# eps-v1-1.net
KiCad netlist of a schematic drawn in EAGLE
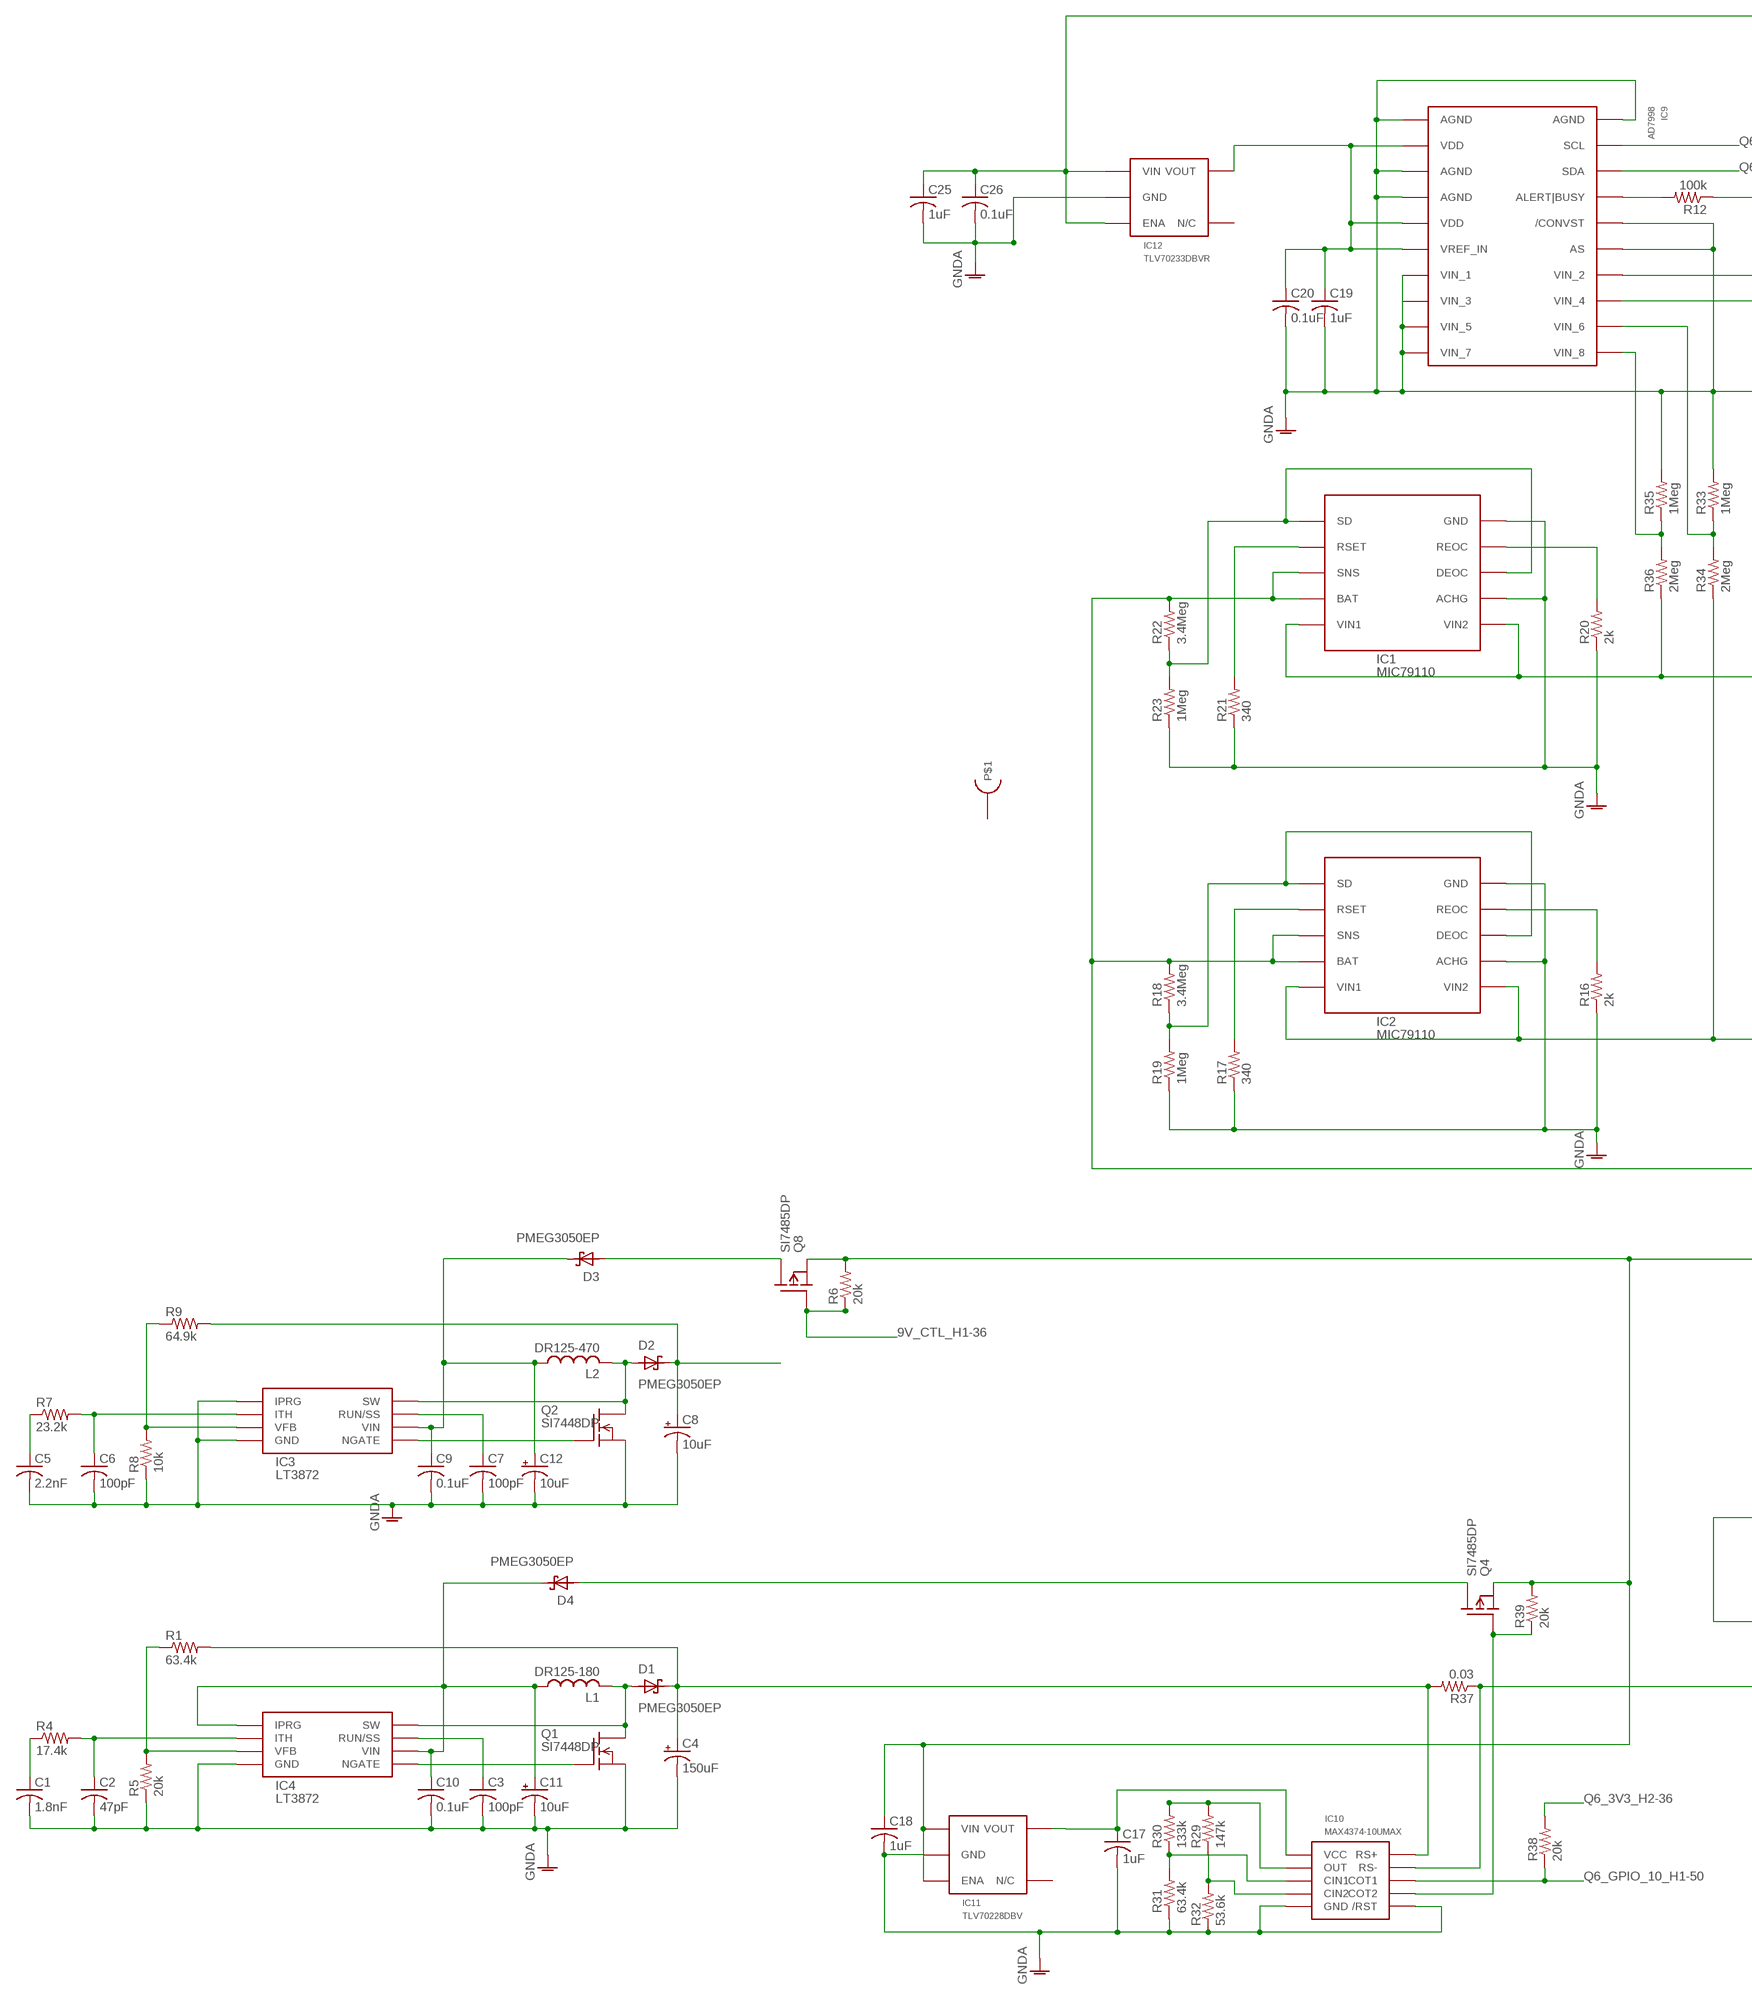
[diagram p0: schematic, sheet 1, part 1 of 2]
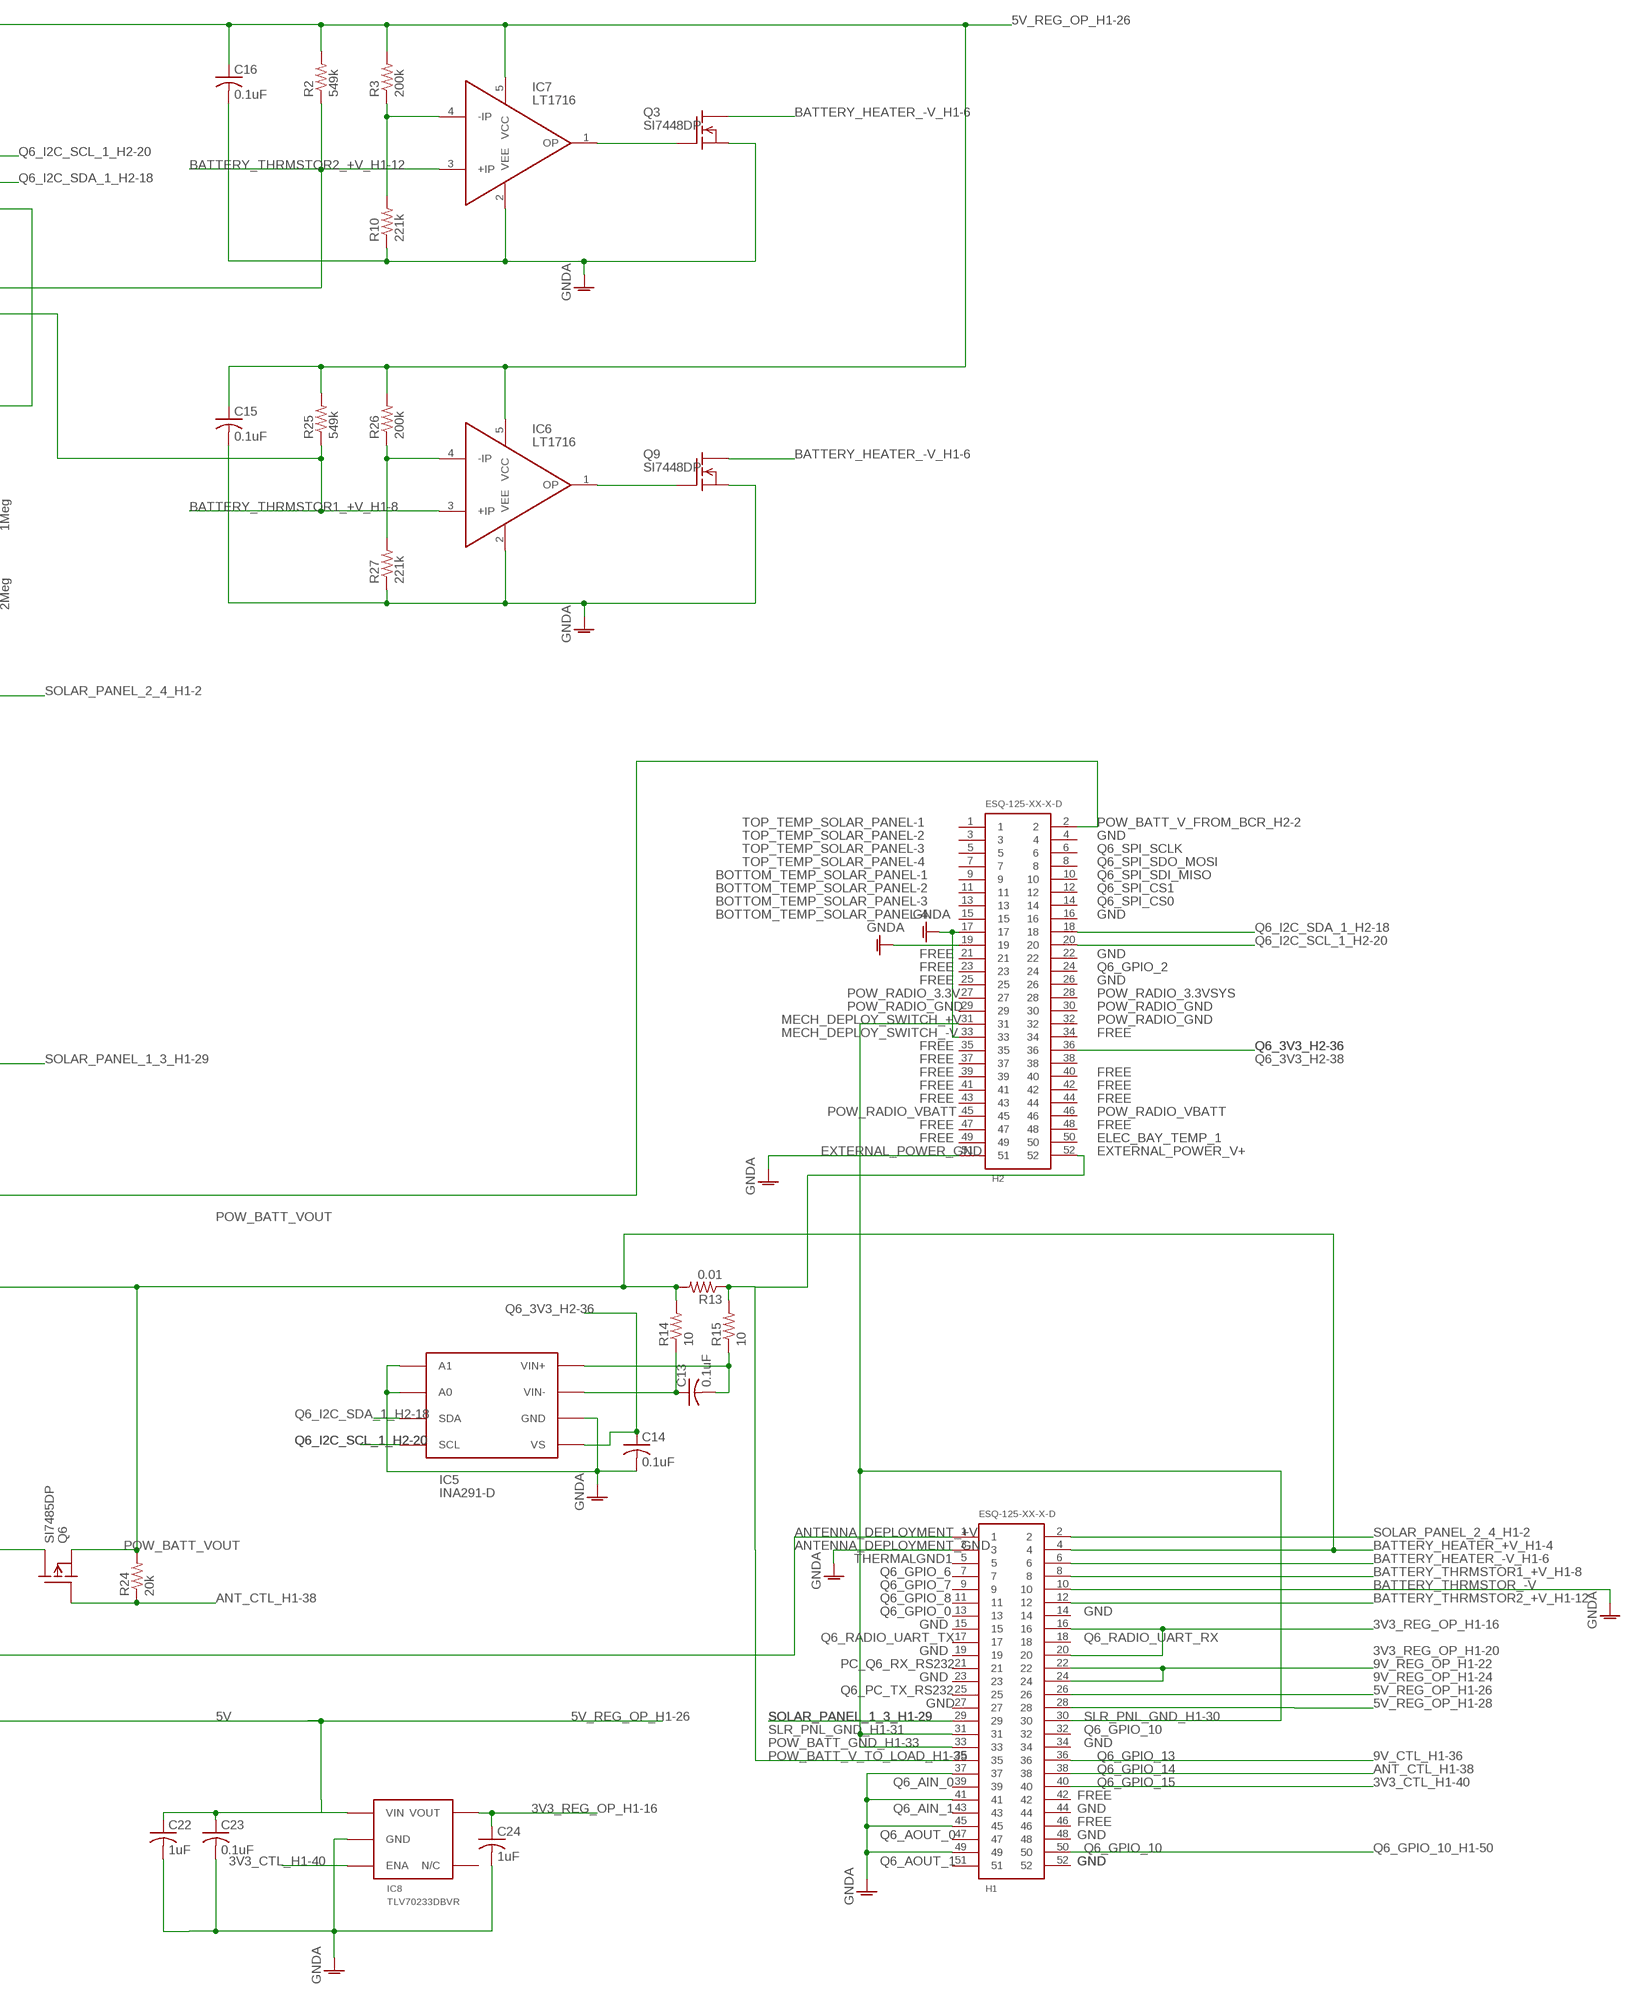
[diagram p1: schematic, sheet 1, part 2 of 2]

(export (version "E")
  (design (tool "Eeschema 10.0.6"))
  (components
    (comp (ref "C1")
      (value "1.8nF")
      (footprint "eagle-import:C0805")
      (libsource (lib "eagle-import") (part "C-USC0805"))
    )
    (comp (ref "C2")
      (value "47pF")
      (footprint "eagle-import:C0805")
      (libsource (lib "eagle-import") (part "C-USC0805"))
    )
    (comp (ref "C3")
      (value "100pF")
      (footprint "eagle-import:C0805")
      (libsource (lib "eagle-import") (part "C-USC0805"))
    )
    (comp (ref "C4")
      (value "150uF")
      (footprint "eagle-import:D_7343-31R")
      (libsource (lib "eagle-import") (part "CPOL-USD/7343-31R"))
    )
    (comp (ref "C5")
      (value "2.2nF")
      (footprint "eagle-import:C0805")
      (libsource (lib "eagle-import") (part "C-USC0805"))
    )
    (comp (ref "C6")
      (value "100pF")
      (footprint "eagle-import:C0805")
      (libsource (lib "eagle-import") (part "C-USC0805"))
    )
    (comp (ref "C7")
      (value "100pF")
      (footprint "eagle-import:C0805")
      (libsource (lib "eagle-import") (part "C-USC0805"))
    )
    (comp (ref "C8")
      (value "10uF")
      (footprint "eagle-import:D_7343-31R")
      (libsource (lib "eagle-import") (part "CPOL-USD/7343-31R"))
    )
    (comp (ref "C9")
      (value "0.1uF")
      (footprint "eagle-import:C0805")
      (libsource (lib "eagle-import") (part "C-USC0805"))
    )
    (comp (ref "C10")
      (value "0.1uF")
      (footprint "eagle-import:C0805")
      (libsource (lib "eagle-import") (part "C-USC0805"))
    )
    (comp (ref "C11")
      (value "10uF")
      (footprint "eagle-import:D_7343-31R")
      (libsource (lib "eagle-import") (part "CPOL-USD/7343-31R"))
    )
    (comp (ref "C12")
      (value "10uF")
      (footprint "eagle-import:D_7343-31R")
      (libsource (lib "eagle-import") (part "CPOL-USD/7343-31R"))
    )
    (comp (ref "C13")
      (value "0.1uF")
      (footprint "eagle-import:C0805")
      (libsource (lib "eagle-import") (part "C-USC0805"))
    )
    (comp (ref "C14")
      (value "0.1uF")
      (footprint "eagle-import:C0805")
      (libsource (lib "eagle-import") (part "C-USC0805"))
    )
    (comp (ref "C15")
      (value "0.1uF")
      (footprint "eagle-import:C0805")
      (libsource (lib "eagle-import") (part "C-USC0805"))
    )
    (comp (ref "C16")
      (value "0.1uF")
      (footprint "eagle-import:C0805")
      (libsource (lib "eagle-import") (part "C-USC0805"))
    )
    (comp (ref "C17")
      (value "1uF")
      (footprint "eagle-import:C0805")
      (libsource (lib "eagle-import") (part "C-USC0805"))
    )
    (comp (ref "C18")
      (value "1uF")
      (footprint "eagle-import:C0805")
      (libsource (lib "eagle-import") (part "C-USC0805"))
    )
    (comp (ref "C19")
      (value "1uF")
      (footprint "eagle-import:C0805")
      (libsource (lib "eagle-import") (part "C-USC0805"))
    )
    (comp (ref "C20")
      (value "0.1uF")
      (footprint "eagle-import:C0805")
      (libsource (lib "eagle-import") (part "C-USC0805"))
    )
    (comp (ref "C22")
      (value "1uF")
      (footprint "eagle-import:C0805")
      (libsource (lib "eagle-import") (part "C-USC0805"))
    )
    (comp (ref "C23")
      (value "0.1uF")
      (footprint "eagle-import:C0805")
      (libsource (lib "eagle-import") (part "C-USC0805"))
    )
    (comp (ref "C24")
      (value "1uF")
      (footprint "eagle-import:C0805")
      (libsource (lib "eagle-import") (part "C-USC0805"))
    )
    (comp (ref "C25")
      (value "1uF")
      (footprint "eagle-import:C0805")
      (libsource (lib "eagle-import") (part "C-USC0805"))
    )
    (comp (ref "C26")
      (value "0.1uF")
      (footprint "eagle-import:C0805")
      (libsource (lib "eagle-import") (part "C-USC0805"))
    )
    (comp (ref "D1")
      (value "PMEG3050EP")
      (footprint "eagle-import:SOD128")
      (libsource (lib "eagle-import") (part "PMEG3050EP"))
    )
    (comp (ref "D2")
      (value "PMEG3050EP")
      (footprint "eagle-import:SOD128")
      (libsource (lib "eagle-import") (part "PMEG3050EP"))
    )
    (comp (ref "D3")
      (value "PMEG3050EP")
      (footprint "eagle-import:SOD128")
      (libsource (lib "eagle-import") (part "PMEG3050EP"))
    )
    (comp (ref "D4")
      (value "PMEG3050EP")
      (footprint "eagle-import:SOD128")
      (libsource (lib "eagle-import") (part "PMEG3050EP"))
    )
    (comp (ref "H1")
      (value "ESQ-125-XX-X-D")
      (footprint "eagle-import:ESQ-125-XX-X-D")
      (libsource (lib "eagle-import") (part "ESQ-125-XX-X-D"))
    )
    (comp (ref "H2")
      (value "ESQ-125-XX-X-D")
      (footprint "eagle-import:ESQ-125-XX-X-D")
      (libsource (lib "eagle-import") (part "ESQ-125-XX-X-D"))
    )
    (comp (ref "IC1")
      (value "MIC79110")
      (footprint "eagle-import:MLF10-EP")
      (libsource (lib "eagle-import") (part "MIC79110"))
    )
    (comp (ref "IC2")
      (value "MIC79110")
      (footprint "eagle-import:MLF10-EP")
      (libsource (lib "eagle-import") (part "MIC79110"))
    )
    (comp (ref "IC3")
      (value "LT3872")
      (footprint "eagle-import:TSOT23-8")
      (libsource (lib "eagle-import") (part "LT3872"))
    )
    (comp (ref "IC4")
      (value "LT3872")
      (footprint "eagle-import:TSOT23-8")
      (libsource (lib "eagle-import") (part "LT3872"))
    )
    (comp (ref "IC5")
      (value "INA291-D")
      (footprint "eagle-import:SO08")
      (libsource (lib "eagle-import") (part "INA291-D"))
    )
    (comp (ref "IC6")
      (value "LT1716")
      (footprint "eagle-import:SOT23-5")
      (libsource (lib "eagle-import") (part "LT1716"))
    )
    (comp (ref "IC7")
      (value "LT1716")
      (footprint "eagle-import:SOT23-5")
      (libsource (lib "eagle-import") (part "LT1716"))
    )
    (comp (ref "IC8")
      (value "TLV70233DBVR")
      (footprint "eagle-import:SOT23-5")
      (libsource (lib "eagle-import") (part "TLV70233DBVR"))
    )
    (comp (ref "IC9")
      (value "AD7998")
      (footprint "eagle-import:TSSOP-20")
      (libsource (lib "eagle-import") (part "AD7998"))
    )
    (comp (ref "IC10")
      (value "MAX4374-10UMAX")
      (footprint "eagle-import:10UMAX")
      (libsource (lib "eagle-import") (part "MAX4374-10UMAX"))
    )
    (comp (ref "IC11")
      (value "TLV70228DBV")
      (footprint "eagle-import:SOT23-5")
      (libsource (lib "eagle-import") (part "TLV70228DBV"))
    )
    (comp (ref "IC12")
      (value "TLV70233DBVR")
      (footprint "eagle-import:SOT23-5")
      (libsource (lib "eagle-import") (part "TLV70233DBVR"))
    )
    (comp (ref "L1")
      (value "DR125-180")
      (footprint "eagle-import:DR125")
      (libsource (lib "eagle-import") (part "DR125-180"))
    )
    (comp (ref "L2")
      (value "DR125-470")
      (footprint "eagle-import:DR125")
      (libsource (lib "eagle-import") (part "DR125-470"))
    )
    (comp (ref "Q1")
      (value "SI7448DP")
      (footprint "eagle-import:PPAK-SO08-EP")
      (libsource (lib "eagle-import") (part "SI7448DP"))
    )
    (comp (ref "Q2")
      (value "SI7448DP")
      (footprint "eagle-import:PPAK-SO08-EP")
      (libsource (lib "eagle-import") (part "SI7448DP"))
    )
    (comp (ref "Q3")
      (value "SI7448DP")
      (footprint "eagle-import:PPAK-SO08-EP")
      (libsource (lib "eagle-import") (part "SI7448DP"))
    )
    (comp (ref "Q4")
      (value "SI7485DP")
      (footprint "eagle-import:PPAK-SO08-EP")
      (libsource (lib "eagle-import") (part "SI7485DP"))
    )
    (comp (ref "Q6")
      (value "SI7485DP")
      (footprint "eagle-import:PPAK-SO08-EP")
      (libsource (lib "eagle-import") (part "SI7485DP"))
    )
    (comp (ref "Q8")
      (value "SI7485DP")
      (footprint "eagle-import:PPAK-SO08-EP")
      (libsource (lib "eagle-import") (part "SI7485DP"))
    )
    (comp (ref "Q9")
      (value "SI7448DP")
      (footprint "eagle-import:PPAK-SO08-EP")
      (libsource (lib "eagle-import") (part "SI7448DP"))
    )
    (comp (ref "R1")
      (value "63.4k")
      (footprint "eagle-import:M1206")
      (libsource (lib "eagle-import") (part "R-US_M1206"))
    )
    (comp (ref "R2")
      (value "549k")
      (footprint "eagle-import:M1206")
      (libsource (lib "eagle-import") (part "R-US_M1206"))
    )
    (comp (ref "R3")
      (value "200k")
      (footprint "eagle-import:M1206")
      (libsource (lib "eagle-import") (part "R-US_M1206"))
    )
    (comp (ref "R4")
      (value "17.4k")
      (footprint "eagle-import:M1206")
      (libsource (lib "eagle-import") (part "R-US_M1206"))
    )
    (comp (ref "R5")
      (value "20k")
      (footprint "eagle-import:M1206")
      (libsource (lib "eagle-import") (part "R-US_M1206"))
    )
    (comp (ref "R6")
      (value "20k")
      (footprint "eagle-import:M1206")
      (libsource (lib "eagle-import") (part "R-US_M1206"))
    )
    (comp (ref "R7")
      (value "23.2k")
      (footprint "eagle-import:M1206")
      (libsource (lib "eagle-import") (part "R-US_M1206"))
    )
    (comp (ref "R8")
      (value "10k")
      (footprint "eagle-import:M1206")
      (libsource (lib "eagle-import") (part "R-US_M1206"))
    )
    (comp (ref "R9")
      (value "64.9k")
      (footprint "eagle-import:M1206")
      (libsource (lib "eagle-import") (part "R-US_M1206"))
    )
    (comp (ref "R10")
      (value "221k")
      (footprint "eagle-import:M1206")
      (libsource (lib "eagle-import") (part "R-US_M1206"))
    )
    (comp (ref "R12")
      (value "100k")
      (footprint "eagle-import:M1206")
      (libsource (lib "eagle-import") (part "R-US_M1206"))
    )
    (comp (ref "R13")
      (value "0.01")
      (footprint "eagle-import:M1206")
      (libsource (lib "eagle-import") (part "R-US_M1206"))
    )
    (comp (ref "R14")
      (value "10")
      (footprint "eagle-import:M1206")
      (libsource (lib "eagle-import") (part "R-US_M1206"))
    )
    (comp (ref "R15")
      (value "10")
      (footprint "eagle-import:M1206")
      (libsource (lib "eagle-import") (part "R-US_M1206"))
    )
    (comp (ref "R16")
      (value "2k")
      (footprint "eagle-import:M1206")
      (libsource (lib "eagle-import") (part "R-US_M1206"))
    )
    (comp (ref "R17")
      (value "340")
      (footprint "eagle-import:M1206")
      (libsource (lib "eagle-import") (part "R-US_M1206"))
    )
    (comp (ref "R18")
      (value "3.4Meg")
      (footprint "eagle-import:M1206")
      (libsource (lib "eagle-import") (part "R-US_M1206"))
    )
    (comp (ref "R19")
      (value "1Meg")
      (footprint "eagle-import:M1206")
      (libsource (lib "eagle-import") (part "R-US_M1206"))
    )
    (comp (ref "R20")
      (value "2k")
      (footprint "eagle-import:M1206")
      (libsource (lib "eagle-import") (part "R-US_M1206"))
    )
    (comp (ref "R21")
      (value "340")
      (footprint "eagle-import:M1206")
      (libsource (lib "eagle-import") (part "R-US_M1206"))
    )
    (comp (ref "R22")
      (value "3.4Meg")
      (footprint "eagle-import:M1206")
      (libsource (lib "eagle-import") (part "R-US_M1206"))
    )
    (comp (ref "R23")
      (value "1Meg")
      (footprint "eagle-import:M1206")
      (libsource (lib "eagle-import") (part "R-US_M1206"))
    )
    (comp (ref "R24")
      (value "20k")
      (footprint "eagle-import:M1206")
      (libsource (lib "eagle-import") (part "R-US_M1206"))
    )
    (comp (ref "R25")
      (value "549k")
      (footprint "eagle-import:M1206")
      (libsource (lib "eagle-import") (part "R-US_M1206"))
    )
    (comp (ref "R26")
      (value "200k")
      (footprint "eagle-import:M1206")
      (libsource (lib "eagle-import") (part "R-US_M1206"))
    )
    (comp (ref "R27")
      (value "221k")
      (footprint "eagle-import:M1206")
      (libsource (lib "eagle-import") (part "R-US_M1206"))
    )
    (comp (ref "R29")
      (value "147k")
      (footprint "eagle-import:M1206")
      (libsource (lib "eagle-import") (part "R-US_M1206"))
    )
    (comp (ref "R30")
      (value "133k")
      (footprint "eagle-import:M1206")
      (libsource (lib "eagle-import") (part "R-US_M1206"))
    )
    (comp (ref "R31")
      (value "63.4k")
      (footprint "eagle-import:M1206")
      (libsource (lib "eagle-import") (part "R-US_M1206"))
    )
    (comp (ref "R32")
      (value "53.6k")
      (footprint "eagle-import:M1206")
      (libsource (lib "eagle-import") (part "R-US_M1206"))
    )
    (comp (ref "R33")
      (value "1Meg")
      (footprint "eagle-import:M1206")
      (libsource (lib "eagle-import") (part "R-US_M1206"))
    )
    (comp (ref "R34")
      (value "2Meg")
      (footprint "eagle-import:M1206")
      (libsource (lib "eagle-import") (part "R-US_M1206"))
    )
    (comp (ref "R35")
      (value "1Meg")
      (footprint "eagle-import:M1206")
      (libsource (lib "eagle-import") (part "R-US_M1206"))
    )
    (comp (ref "R36")
      (value "2Meg")
      (footprint "eagle-import:M1206")
      (libsource (lib "eagle-import") (part "R-US_M1206"))
    )
    (comp (ref "R37")
      (value "0.03")
      (footprint "eagle-import:M1206")
      (libsource (lib "eagle-import") (part "R-US_M1206"))
    )
    (comp (ref "R38")
      (value "20k")
      (footprint "eagle-import:M1206")
      (libsource (lib "eagle-import") (part "R-US_M1206"))
    )
    (comp (ref "R39")
      (value "20k")
      (footprint "eagle-import:M1206")
      (libsource (lib "eagle-import") (part "R-US_M1206"))
    )
    (comp (ref "U$1")
      (value "EPS_PCB_THRM_PAD")
      (footprint "eagle-import:EPS_PCB_THRM_PAD")
      (libsource (lib "eagle-import") (part "EPS_PCB_THRM_PAD"))
    )
  )
  (nets
    (net (code "1") (name "/3V3_CTL_H1-40") (class "Default")
      (node (ref "H1") (pin "40") (pinfunction "40_40") (pintype "bidirectional"))
      (node (ref "IC8") (pin "3") (pinfunction "ENA_3") (pintype "bidirectional"))
    )
    (net (code "2") (name "/3V3_REG_OP_H1-16") (class "Default")
      (node (ref "C24") (pin "1") (pinfunction "1_1") (pintype "passive"))
      (node (ref "H1") (pin "16") (pinfunction "16_16") (pintype "bidirectional"))
      (node (ref "H1") (pin "20") (pinfunction "20_20") (pintype "bidirectional"))
      (node (ref "IC8") (pin "5") (pinfunction "VOUT_5") (pintype "bidirectional"))
    )
    (net (code "3") (name "/5V_REG_OP_H1-26") (class "Default")
      (node (ref "C15") (pin "1") (pinfunction "1_1") (pintype "passive"))
      (node (ref "C16") (pin "1") (pinfunction "1_1") (pintype "passive"))
      (node (ref "C22") (pin "1") (pinfunction "1_1") (pintype "passive"))
      (node (ref "C23") (pin "1") (pinfunction "1_1") (pintype "passive"))
      (node (ref "C25") (pin "1") (pinfunction "1_1") (pintype "passive"))
      (node (ref "C26") (pin "1") (pinfunction "1_1") (pintype "passive"))
      (node (ref "H1") (pin "26") (pinfunction "26_26") (pintype "bidirectional"))
      (node (ref "H1") (pin "28") (pinfunction "28_28") (pintype "bidirectional"))
      (node (ref "IC10") (pin "P$9") (pinfunction "RS-_P$9") (pintype "bidirectional"))
      (node (ref "IC12") (pin "1") (pinfunction "VIN_1") (pintype "bidirectional"))
      (node (ref "IC12") (pin "3") (pinfunction "ENA_3") (pintype "bidirectional"))
      (node (ref "IC6") (pin "5") (pinfunction "VCC_5") (pintype "bidirectional"))
      (node (ref "IC7") (pin "5") (pinfunction "VCC_5") (pintype "bidirectional"))
      (node (ref "IC8") (pin "1") (pinfunction "VIN_1") (pintype "bidirectional"))
      (node (ref "R2") (pin "2") (pinfunction "2_2") (pintype "passive"))
      (node (ref "R25") (pin "2") (pinfunction "2_2") (pintype "passive"))
      (node (ref "R26") (pin "2") (pinfunction "2_2") (pintype "passive"))
      (node (ref "R3") (pin "2") (pinfunction "2_2") (pintype "passive"))
      (node (ref "R37") (pin "1") (pinfunction "1_1") (pintype "passive"))
    )
    (net (code "4") (name "/9V_CTL_H1-36") (class "Default")
      (node (ref "H1") (pin "36") (pinfunction "36_36") (pintype "bidirectional"))
      (node (ref "Q8") (pin "P$4-G") (pinfunction "G_P$4-G") (pintype "passive"))
      (node (ref "R6") (pin "1") (pinfunction "1_1") (pintype "passive"))
    )
    (net (code "5") (name "/9V_REG_OP_H1-22") (class "Default")
      (node (ref "C8") (pin "+") (pinfunction "+_+") (pintype "passive"))
      (node (ref "D2") (pin "P$1-CATHODE") (pinfunction "P$1-CATHODE_P$1-CATHODE") (pintype "bidirectional"))
      (node (ref "H1") (pin "22") (pinfunction "22_22") (pintype "bidirectional"))
      (node (ref "H1") (pin "24") (pinfunction "24_24") (pintype "bidirectional"))
      (node (ref "R9") (pin "2") (pinfunction "2_2") (pintype "passive"))
    )
    (net (code "6") (name "/ANT_CTL_H1-38") (class "Default")
      (node (ref "H1") (pin "38") (pinfunction "38_38") (pintype "bidirectional"))
      (node (ref "Q6") (pin "P$4-G") (pinfunction "G_P$4-G") (pintype "passive"))
      (node (ref "R24") (pin "1") (pinfunction "1_1") (pintype "passive"))
    )
    (net (code "7") (name "/BATTERY_HEATER_-V_H1-6") (class "Default")
      (node (ref "H1") (pin "6") (pinfunction "6_6") (pintype "bidirectional"))
      (node (ref "Q3") (pin "P$10-D") (pinfunction "D_P$10-D") (pintype "passive"))
      (node (ref "Q3") (pin "P$11-D") (pinfunction "D_P$11-D") (pintype "passive"))
      (node (ref "Q3") (pin "P$5-D") (pinfunction "D_P$5-D") (pintype "passive"))
      (node (ref "Q3") (pin "P$6-D") (pinfunction "D_P$6-D") (pintype "passive"))
      (node (ref "Q3") (pin "P$7-D") (pinfunction "D_P$7-D") (pintype "passive"))
      (node (ref "Q3") (pin "P$8-D") (pinfunction "D_P$8-D") (pintype "passive"))
      (node (ref "Q3") (pin "P$9-D") (pinfunction "D_P$9-D") (pintype "passive"))
      (node (ref "Q9") (pin "P$10-D") (pinfunction "D_P$10-D") (pintype "passive"))
      (node (ref "Q9") (pin "P$11-D") (pinfunction "D_P$11-D") (pintype "passive"))
      (node (ref "Q9") (pin "P$5-D") (pinfunction "D_P$5-D") (pintype "passive"))
      (node (ref "Q9") (pin "P$6-D") (pinfunction "D_P$6-D") (pintype "passive"))
      (node (ref "Q9") (pin "P$7-D") (pinfunction "D_P$7-D") (pintype "passive"))
      (node (ref "Q9") (pin "P$8-D") (pinfunction "D_P$8-D") (pintype "passive"))
      (node (ref "Q9") (pin "P$9-D") (pinfunction "D_P$9-D") (pintype "passive"))
    )
    (net (code "8") (name "/BATTERY_THRMSTOR1_+V_H1-8") (class "Default")
      (node (ref "H1") (pin "8") (pinfunction "8_8") (pintype "bidirectional"))
      (node (ref "IC6") (pin "3") (pinfunction "+IP_3") (pintype "bidirectional"))
      (node (ref "IC9") (pin "P$13") (pinfunction "VIN_4_P$13") (pintype "bidirectional"))
      (node (ref "R25") (pin "1") (pinfunction "1_1") (pintype "passive"))
    )
    (net (code "9") (name "/BATTERY_THRMSTOR2_+V_H1-12") (class "Default")
      (node (ref "H1") (pin "12") (pinfunction "12_12") (pintype "bidirectional"))
      (node (ref "IC7") (pin "3") (pinfunction "+IP_3") (pintype "bidirectional"))
      (node (ref "IC9") (pin "P$14") (pinfunction "VIN_2_P$14") (pintype "bidirectional"))
      (node (ref "R2") (pin "1") (pinfunction "1_1") (pintype "passive"))
    )
    (net (code "10") (name "/Q6_3V3_H2-36") (class "Default")
      (node (ref "C14") (pin "1") (pinfunction "1_1") (pintype "passive"))
      (node (ref "H2") (pin "36") (pinfunction "36_36") (pintype "bidirectional"))
      (node (ref "IC5") (pin "5") (pinfunction "VS_5") (pintype "bidirectional"))
      (node (ref "R38") (pin "2") (pinfunction "2_2") (pintype "passive"))
    )
    (net (code "11") (name "/Q6_GPIO_10_H1-50") (class "Default")
      (node (ref "H1") (pin "50") (pinfunction "50_50") (pintype "bidirectional"))
      (node (ref "IC10") (pin "P$8") (pinfunction "COT1_P$8") (pintype "bidirectional"))
      (node (ref "R38") (pin "1") (pinfunction "1_1") (pintype "passive"))
    )
    (net (code "12") (name "/Q6_I2C_SCL_1_H2-20") (class "Default")
      (node (ref "H2") (pin "20") (pinfunction "20_20") (pintype "bidirectional"))
      (node (ref "IC5") (pin "4") (pinfunction "SCL_4") (pintype "bidirectional"))
      (node (ref "IC9") (pin "P$19") (pinfunction "SCL_P$19") (pintype "bidirectional"))
    )
    (net (code "13") (name "/Q6_I2C_SDA_1_H2-18") (class "Default")
      (node (ref "H2") (pin "18") (pinfunction "18_18") (pintype "bidirectional"))
      (node (ref "IC5") (pin "3") (pinfunction "SDA_3") (pintype "bidirectional"))
      (node (ref "IC9") (pin "P$18") (pinfunction "SDA_P$18") (pintype "bidirectional"))
    )
    (net (code "14") (name "/SOLAR_PANEL_1_3_H1-29") (class "Default")
      (node (ref "H1") (pin "29") (pinfunction "29_29") (pintype "bidirectional"))
      (node (ref "IC2") (pin "P$5") (pinfunction "VIN1_P$5") (pintype "bidirectional"))
      (node (ref "IC2") (pin "P$6") (pinfunction "VIN2_P$6") (pintype "bidirectional"))
      (node (ref "R34") (pin "1") (pinfunction "1_1") (pintype "passive"))
    )
    (net (code "15") (name "/SOLAR_PANEL_2_4_H1-2") (class "Default")
      (node (ref "H1") (pin "2") (pinfunction "2_2") (pintype "bidirectional"))
      (node (ref "IC1") (pin "P$5") (pinfunction "VIN1_P$5") (pintype "bidirectional"))
      (node (ref "IC1") (pin "P$6") (pinfunction "VIN2_P$6") (pintype "bidirectional"))
      (node (ref "R36") (pin "1") (pinfunction "1_1") (pintype "passive"))
    )
    (net (code "16") (name "GNDA") (class "Default")
      (node (ref "C1") (pin "2") (pinfunction "2_2") (pintype "passive"))
      (node (ref "C10") (pin "2") (pinfunction "2_2") (pintype "passive"))
      (node (ref "C11") (pin "-") (pinfunction "-_-") (pintype "passive"))
      (node (ref "C12") (pin "-") (pinfunction "-_-") (pintype "passive"))
      (node (ref "C14") (pin "2") (pinfunction "2_2") (pintype "passive"))
      (node (ref "C15") (pin "2") (pinfunction "2_2") (pintype "passive"))
      (node (ref "C16") (pin "2") (pinfunction "2_2") (pintype "passive"))
      (node (ref "C17") (pin "2") (pinfunction "2_2") (pintype "passive"))
      (node (ref "C18") (pin "2") (pinfunction "2_2") (pintype "passive"))
      (node (ref "C19") (pin "2") (pinfunction "2_2") (pintype "passive"))
      (node (ref "C2") (pin "2") (pinfunction "2_2") (pintype "passive"))
      (node (ref "C20") (pin "2") (pinfunction "2_2") (pintype "passive"))
      (node (ref "C22") (pin "2") (pinfunction "2_2") (pintype "passive"))
      (node (ref "C23") (pin "2") (pinfunction "2_2") (pintype "passive"))
      (node (ref "C24") (pin "2") (pinfunction "2_2") (pintype "passive"))
      (node (ref "C25") (pin "2") (pinfunction "2_2") (pintype "passive"))
      (node (ref "C26") (pin "2") (pinfunction "2_2") (pintype "passive"))
      (node (ref "C3") (pin "2") (pinfunction "2_2") (pintype "passive"))
      (node (ref "C4") (pin "-") (pinfunction "-_-") (pintype "passive"))
      (node (ref "C5") (pin "2") (pinfunction "2_2") (pintype "passive"))
      (node (ref "C6") (pin "2") (pinfunction "2_2") (pintype "passive"))
      (node (ref "C7") (pin "2") (pinfunction "2_2") (pintype "passive"))
      (node (ref "C8") (pin "-") (pinfunction "-_-") (pintype "passive"))
      (node (ref "C9") (pin "2") (pinfunction "2_2") (pintype "passive"))
      (node (ref "H1") (pin "10") (pinfunction "10_10") (pintype "bidirectional"))
      (node (ref "H1") (pin "3") (pinfunction "3_3") (pintype "bidirectional"))
      (node (ref "H1") (pin "37") (pinfunction "37_37") (pintype "bidirectional"))
      (node (ref "H1") (pin "41") (pinfunction "41_41") (pintype "bidirectional"))
      (node (ref "H1") (pin "45") (pinfunction "45_45") (pintype "bidirectional"))
      (node (ref "H1") (pin "49") (pinfunction "49_49") (pintype "bidirectional"))
      (node (ref "H2") (pin "17") (pinfunction "17_17") (pintype "bidirectional"))
      (node (ref "H2") (pin "19") (pinfunction "19_19") (pintype "bidirectional"))
      (node (ref "H2") (pin "33") (pinfunction "33_33") (pintype "bidirectional"))
      (node (ref "H2") (pin "51") (pinfunction "51_51") (pintype "bidirectional"))
      (node (ref "IC1") (pin "P$10") (pinfunction "GND_P$10") (pintype "bidirectional"))
      (node (ref "IC1") (pin "P$7") (pinfunction "ACHG_P$7") (pintype "bidirectional"))
      (node (ref "IC10") (pin "P$5") (pinfunction "GND_P$5") (pintype "bidirectional"))
      (node (ref "IC10") (pin "P$6") (pinfunction "/RST_P$6") (pintype "bidirectional"))
      (node (ref "IC11") (pin "2") (pinfunction "GND_2") (pintype "bidirectional"))
      (node (ref "IC12") (pin "2") (pinfunction "GND_2") (pintype "bidirectional"))
      (node (ref "IC2") (pin "P$10") (pinfunction "GND_P$10") (pintype "bidirectional"))
      (node (ref "IC2") (pin "P$7") (pinfunction "ACHG_P$7") (pintype "bidirectional"))
      (node (ref "IC3") (pin "P$1") (pinfunction "IPRG_P$1") (pintype "bidirectional"))
      (node (ref "IC3") (pin "P$4") (pinfunction "GND_P$4") (pintype "bidirectional"))
      (node (ref "IC4") (pin "P$4") (pinfunction "GND_P$4") (pintype "bidirectional"))
      (node (ref "IC5") (pin "1") (pinfunction "A1_1") (pintype "bidirectional"))
      (node (ref "IC5") (pin "2") (pinfunction "A0_2") (pintype "bidirectional"))
      (node (ref "IC5") (pin "6") (pinfunction "GND_6") (pintype "bidirectional"))
      (node (ref "IC6") (pin "2") (pinfunction "VEE_2") (pintype "bidirectional"))
      (node (ref "IC7") (pin "2") (pinfunction "VEE_2") (pintype "bidirectional"))
      (node (ref "IC8") (pin "2") (pinfunction "GND_2") (pintype "bidirectional"))
      (node (ref "IC9") (pin "P$1") (pinfunction "AGND_P$1") (pintype "bidirectional"))
      (node (ref "IC9") (pin "P$10") (pinfunction "VIN_7_P$10") (pintype "bidirectional"))
      (node (ref "IC9") (pin "P$15") (pinfunction "AS_P$15") (pintype "bidirectional"))
      (node (ref "IC9") (pin "P$16") (pinfunction "/CONVST_P$16") (pintype "bidirectional"))
      (node (ref "IC9") (pin "P$20") (pinfunction "AGND_P$20") (pintype "bidirectional"))
      (node (ref "IC9") (pin "P$3") (pinfunction "AGND_P$3") (pintype "bidirectional"))
      (node (ref "IC9") (pin "P$4") (pinfunction "AGND_P$4") (pintype "bidirectional"))
      (node (ref "IC9") (pin "P$7") (pinfunction "VIN_1_P$7") (pintype "bidirectional"))
      (node (ref "IC9") (pin "P$8") (pinfunction "VIN_3_P$8") (pintype "bidirectional"))
      (node (ref "IC9") (pin "P$9") (pinfunction "VIN_5_P$9") (pintype "bidirectional"))
      (node (ref "Q1") (pin "P$1-S") (pinfunction "S_P$1-S") (pintype "passive"))
      (node (ref "Q1") (pin "P$2-S") (pinfunction "S_P$2-S") (pintype "passive"))
      (node (ref "Q1") (pin "P$3-S") (pinfunction "S_P$3-S") (pintype "passive"))
      (node (ref "Q2") (pin "P$1-S") (pinfunction "S_P$1-S") (pintype "passive"))
      (node (ref "Q2") (pin "P$2-S") (pinfunction "S_P$2-S") (pintype "passive"))
      (node (ref "Q2") (pin "P$3-S") (pinfunction "S_P$3-S") (pintype "passive"))
      (node (ref "Q3") (pin "P$1-S") (pinfunction "S_P$1-S") (pintype "passive"))
      (node (ref "Q3") (pin "P$2-S") (pinfunction "S_P$2-S") (pintype "passive"))
      (node (ref "Q3") (pin "P$3-S") (pinfunction "S_P$3-S") (pintype "passive"))
      (node (ref "Q9") (pin "P$1-S") (pinfunction "S_P$1-S") (pintype "passive"))
      (node (ref "Q9") (pin "P$2-S") (pinfunction "S_P$2-S") (pintype "passive"))
      (node (ref "Q9") (pin "P$3-S") (pinfunction "S_P$3-S") (pintype "passive"))
      (node (ref "R10") (pin "1") (pinfunction "1_1") (pintype "passive"))
      (node (ref "R12") (pin "1") (pinfunction "1_1") (pintype "passive"))
      (node (ref "R16") (pin "1") (pinfunction "1_1") (pintype "passive"))
      (node (ref "R17") (pin "1") (pinfunction "1_1") (pintype "passive"))
      (node (ref "R19") (pin "1") (pinfunction "1_1") (pintype "passive"))
      (node (ref "R20") (pin "1") (pinfunction "1_1") (pintype "passive"))
      (node (ref "R21") (pin "1") (pinfunction "1_1") (pintype "passive"))
      (node (ref "R23") (pin "1") (pinfunction "1_1") (pintype "passive"))
      (node (ref "R27") (pin "1") (pinfunction "1_1") (pintype "passive"))
      (node (ref "R31") (pin "1") (pinfunction "1_1") (pintype "passive"))
      (node (ref "R32") (pin "1") (pinfunction "1_1") (pintype "passive"))
      (node (ref "R33") (pin "2") (pinfunction "2_2") (pintype "passive"))
      (node (ref "R35") (pin "2") (pinfunction "2_2") (pintype "passive"))
      (node (ref "R5") (pin "1") (pinfunction "1_1") (pintype "passive"))
      (node (ref "R8") (pin "1") (pinfunction "1_1") (pintype "passive"))
    )
    (net (code "17") (name "Net-(C1-Pad1)") (class "Default")
      (node (ref "C1") (pin "1") (pinfunction "1_1") (pintype "passive"))
      (node (ref "R4") (pin "1") (pinfunction "1_1") (pintype "passive"))
    )
    (net (code "18") (name "Net-(C5-Pad1)") (class "Default")
      (node (ref "C5") (pin "1") (pinfunction "1_1") (pintype "passive"))
      (node (ref "R7") (pin "1") (pinfunction "1_1") (pintype "passive"))
    )
    (net (code "19") (name "Net-(D3-PadP$2-ANODE)") (class "Default")
      (node (ref "D3") (pin "P$2-ANODE") (pinfunction "P$2-ANODE_P$2-ANODE") (pintype "bidirectional"))
      (node (ref "Q8") (pin "P$10-D") (pinfunction "D_P$10-D") (pintype "passive"))
      (node (ref "Q8") (pin "P$11-D") (pinfunction "D_P$11-D") (pintype "passive"))
      (node (ref "Q8") (pin "P$5-D") (pinfunction "D_P$5-D") (pintype "passive"))
      (node (ref "Q8") (pin "P$6-D") (pinfunction "D_P$6-D") (pintype "passive"))
      (node (ref "Q8") (pin "P$7-D") (pinfunction "D_P$7-D") (pintype "passive"))
      (node (ref "Q8") (pin "P$8-D") (pinfunction "D_P$8-D") (pintype "passive"))
      (node (ref "Q8") (pin "P$9-D") (pinfunction "D_P$9-D") (pintype "passive"))
    )
    (net (code "20") (name "Net-(D4-PadP$2-ANODE)") (class "Default")
      (node (ref "D4") (pin "P$2-ANODE") (pinfunction "P$2-ANODE_P$2-ANODE") (pintype "bidirectional"))
      (node (ref "Q4") (pin "P$10-D") (pinfunction "D_P$10-D") (pintype "passive"))
      (node (ref "Q4") (pin "P$11-D") (pinfunction "D_P$11-D") (pintype "passive"))
      (node (ref "Q4") (pin "P$5-D") (pinfunction "D_P$5-D") (pintype "passive"))
      (node (ref "Q4") (pin "P$6-D") (pinfunction "D_P$6-D") (pintype "passive"))
      (node (ref "Q4") (pin "P$7-D") (pinfunction "D_P$7-D") (pintype "passive"))
      (node (ref "Q4") (pin "P$8-D") (pinfunction "D_P$8-D") (pintype "passive"))
      (node (ref "Q4") (pin "P$9-D") (pinfunction "D_P$9-D") (pintype "passive"))
    )
    (net (code "21") (name "Net-(H1-Pad1)") (class "Default")
      (node (ref "H1") (pin "1") (pinfunction "1_1") (pintype "bidirectional"))
      (node (ref "Q6") (pin "P$10-D") (pinfunction "D_P$10-D") (pintype "passive"))
      (node (ref "Q6") (pin "P$11-D") (pinfunction "D_P$11-D") (pintype "passive"))
      (node (ref "Q6") (pin "P$5-D") (pinfunction "D_P$5-D") (pintype "passive"))
      (node (ref "Q6") (pin "P$6-D") (pinfunction "D_P$6-D") (pintype "passive"))
      (node (ref "Q6") (pin "P$7-D") (pinfunction "D_P$7-D") (pintype "passive"))
      (node (ref "Q6") (pin "P$8-D") (pinfunction "D_P$8-D") (pintype "passive"))
      (node (ref "Q6") (pin "P$9-D") (pinfunction "D_P$9-D") (pintype "passive"))
    )
    (net (code "22") (name "Net-(H1-Pad30)") (class "Default")
      (node (ref "H1") (pin "30") (pinfunction "30_30") (pintype "bidirectional"))
      (node (ref "H1") (pin "31") (pinfunction "31_31") (pintype "bidirectional"))
      (node (ref "H1") (pin "33") (pinfunction "33_33") (pintype "bidirectional"))
      (node (ref "H2") (pin "31") (pinfunction "31_31") (pintype "bidirectional"))
    )
    (net (code "23") (name "Net-(H1-Pad35)") (class "Default")
      (node (ref "H1") (pin "35") (pinfunction "35_35") (pintype "bidirectional"))
      (node (ref "H2") (pin "52") (pinfunction "52_52") (pintype "bidirectional"))
      (node (ref "R13") (pin "1") (pinfunction "1_1") (pintype "passive"))
      (node (ref "R15") (pin "2") (pinfunction "2_2") (pintype "passive"))
    )
    (net (code "24") (name "Net-(IC1-BAT)") (class "Default")
      (node (ref "H2") (pin "2") (pinfunction "2_2") (pintype "bidirectional"))
      (node (ref "IC1") (pin "P$3") (pinfunction "SNS_P$3") (pintype "bidirectional"))
      (node (ref "IC1") (pin "P$4") (pinfunction "BAT_P$4") (pintype "bidirectional"))
      (node (ref "IC2") (pin "P$3") (pinfunction "SNS_P$3") (pintype "bidirectional"))
      (node (ref "IC2") (pin "P$4") (pinfunction "BAT_P$4") (pintype "bidirectional"))
      (node (ref "R18") (pin "2") (pinfunction "2_2") (pintype "passive"))
      (node (ref "R22") (pin "2") (pinfunction "2_2") (pintype "passive"))
    )
    (net (code "25") (name "Net-(IC1-DEOC)") (class "Default")
      (node (ref "IC1") (pin "P$1") (pinfunction "SD_P$1") (pintype "bidirectional"))
      (node (ref "IC1") (pin "P$8") (pinfunction "DEOC_P$8") (pintype "bidirectional"))
      (node (ref "R22") (pin "1") (pinfunction "1_1") (pintype "passive"))
      (node (ref "R23") (pin "2") (pinfunction "2_2") (pintype "passive"))
    )
    (net (code "26") (name "Net-(IC1-REOC)") (class "Default")
      (node (ref "IC1") (pin "P$9") (pinfunction "REOC_P$9") (pintype "bidirectional"))
      (node (ref "R20") (pin "2") (pinfunction "2_2") (pintype "passive"))
    )
    (net (code "27") (name "Net-(IC1-RSET)") (class "Default")
      (node (ref "IC1") (pin "P$2") (pinfunction "RSET_P$2") (pintype "bidirectional"))
      (node (ref "R21") (pin "2") (pinfunction "2_2") (pintype "passive"))
    )
    (net (code "28") (name "Net-(IC2-DEOC)") (class "Default")
      (node (ref "IC2") (pin "P$1") (pinfunction "SD_P$1") (pintype "bidirectional"))
      (node (ref "IC2") (pin "P$8") (pinfunction "DEOC_P$8") (pintype "bidirectional"))
      (node (ref "R18") (pin "1") (pinfunction "1_1") (pintype "passive"))
      (node (ref "R19") (pin "2") (pinfunction "2_2") (pintype "passive"))
    )
    (net (code "29") (name "Net-(IC2-REOC)") (class "Default")
      (node (ref "IC2") (pin "P$9") (pinfunction "REOC_P$9") (pintype "bidirectional"))
      (node (ref "R16") (pin "2") (pinfunction "2_2") (pintype "passive"))
    )
    (net (code "30") (name "Net-(IC2-RSET)") (class "Default")
      (node (ref "IC2") (pin "P$2") (pinfunction "RSET_P$2") (pintype "bidirectional"))
      (node (ref "R17") (pin "2") (pinfunction "2_2") (pintype "passive"))
    )
    (net (code "31") (name "Net-(IC3-ITH)") (class "Default")
      (node (ref "C6") (pin "1") (pinfunction "1_1") (pintype "passive"))
      (node (ref "IC3") (pin "P$2") (pinfunction "ITH_P$2") (pintype "bidirectional"))
      (node (ref "R7") (pin "2") (pinfunction "2_2") (pintype "passive"))
    )
    (net (code "32") (name "Net-(IC3-NGATE)") (class "Default")
      (node (ref "IC3") (pin "P$5") (pinfunction "NGATE_P$5") (pintype "bidirectional"))
      (node (ref "Q2") (pin "P$4-G") (pinfunction "G_P$4-G") (pintype "passive"))
    )
    (net (code "33") (name "Net-(IC3-RUN{slash}SS)") (class "Default")
      (node (ref "C7") (pin "1") (pinfunction "1_1") (pintype "passive"))
      (node (ref "IC3") (pin "P$7") (pinfunction "RUN/SS_P$7") (pintype "bidirectional"))
    )
    (net (code "34") (name "Net-(IC3-SW)") (class "Default")
      (node (ref "D2") (pin "P$2-ANODE") (pinfunction "P$2-ANODE_P$2-ANODE") (pintype "bidirectional"))
      (node (ref "IC3") (pin "P$8") (pinfunction "SW_P$8") (pintype "bidirectional"))
      (node (ref "L2") (pin "P$2") (pinfunction "2_P$2") (pintype "passive"))
      (node (ref "Q2") (pin "P$10-D") (pinfunction "D_P$10-D") (pintype "passive"))
      (node (ref "Q2") (pin "P$11-D") (pinfunction "D_P$11-D") (pintype "passive"))
      (node (ref "Q2") (pin "P$5-D") (pinfunction "D_P$5-D") (pintype "passive"))
      (node (ref "Q2") (pin "P$6-D") (pinfunction "D_P$6-D") (pintype "passive"))
      (node (ref "Q2") (pin "P$7-D") (pinfunction "D_P$7-D") (pintype "passive"))
      (node (ref "Q2") (pin "P$8-D") (pinfunction "D_P$8-D") (pintype "passive"))
      (node (ref "Q2") (pin "P$9-D") (pinfunction "D_P$9-D") (pintype "passive"))
    )
    (net (code "35") (name "Net-(IC3-VFB)") (class "Default")
      (node (ref "IC3") (pin "P$3") (pinfunction "VFB_P$3") (pintype "bidirectional"))
      (node (ref "R8") (pin "2") (pinfunction "2_2") (pintype "passive"))
      (node (ref "R9") (pin "1") (pinfunction "1_1") (pintype "passive"))
    )
    (net (code "36") (name "Net-(IC3-VIN)") (class "Default")
      (node (ref "C12") (pin "+") (pinfunction "+_+") (pintype "passive"))
      (node (ref "C9") (pin "1") (pinfunction "1_1") (pintype "passive"))
      (node (ref "D3") (pin "P$1-CATHODE") (pinfunction "P$1-CATHODE_P$1-CATHODE") (pintype "bidirectional"))
      (node (ref "IC3") (pin "P$6") (pinfunction "VIN_P$6") (pintype "bidirectional"))
      (node (ref "L2") (pin "P$1") (pinfunction "1_P$1") (pintype "passive"))
    )
    (net (code "37") (name "Net-(IC4-IPRG)") (class "Default")
      (node (ref "C10") (pin "1") (pinfunction "1_1") (pintype "passive"))
      (node (ref "C11") (pin "+") (pinfunction "+_+") (pintype "passive"))
      (node (ref "D4") (pin "P$1-CATHODE") (pinfunction "P$1-CATHODE_P$1-CATHODE") (pintype "bidirectional"))
      (node (ref "IC4") (pin "P$1") (pinfunction "IPRG_P$1") (pintype "bidirectional"))
      (node (ref "IC4") (pin "P$6") (pinfunction "VIN_P$6") (pintype "bidirectional"))
      (node (ref "L1") (pin "P$1") (pinfunction "1_P$1") (pintype "passive"))
    )
    (net (code "38") (name "Net-(IC4-ITH)") (class "Default")
      (node (ref "C2") (pin "1") (pinfunction "1_1") (pintype "passive"))
      (node (ref "IC4") (pin "P$2") (pinfunction "ITH_P$2") (pintype "bidirectional"))
      (node (ref "R4") (pin "2") (pinfunction "2_2") (pintype "passive"))
    )
    (net (code "39") (name "Net-(IC4-NGATE)") (class "Default")
      (node (ref "IC4") (pin "P$5") (pinfunction "NGATE_P$5") (pintype "bidirectional"))
      (node (ref "Q1") (pin "P$4-G") (pinfunction "G_P$4-G") (pintype "passive"))
    )
    (net (code "40") (name "Net-(IC4-RUN{slash}SS)") (class "Default")
      (node (ref "C3") (pin "1") (pinfunction "1_1") (pintype "passive"))
      (node (ref "IC4") (pin "P$7") (pinfunction "RUN/SS_P$7") (pintype "bidirectional"))
    )
    (net (code "41") (name "Net-(IC4-SW)") (class "Default")
      (node (ref "D1") (pin "P$2-ANODE") (pinfunction "P$2-ANODE_P$2-ANODE") (pintype "bidirectional"))
      (node (ref "IC4") (pin "P$8") (pinfunction "SW_P$8") (pintype "bidirectional"))
      (node (ref "L1") (pin "P$2") (pinfunction "2_P$2") (pintype "passive"))
      (node (ref "Q1") (pin "P$10-D") (pinfunction "D_P$10-D") (pintype "passive"))
      (node (ref "Q1") (pin "P$11-D") (pinfunction "D_P$11-D") (pintype "passive"))
      (node (ref "Q1") (pin "P$5-D") (pinfunction "D_P$5-D") (pintype "passive"))
      (node (ref "Q1") (pin "P$6-D") (pinfunction "D_P$6-D") (pintype "passive"))
      (node (ref "Q1") (pin "P$7-D") (pinfunction "D_P$7-D") (pintype "passive"))
      (node (ref "Q1") (pin "P$8-D") (pinfunction "D_P$8-D") (pintype "passive"))
      (node (ref "Q1") (pin "P$9-D") (pinfunction "D_P$9-D") (pintype "passive"))
    )
    (net (code "42") (name "Net-(IC4-VFB)") (class "Default")
      (node (ref "IC4") (pin "P$3") (pinfunction "VFB_P$3") (pintype "bidirectional"))
      (node (ref "R1") (pin "1") (pinfunction "1_1") (pintype "passive"))
      (node (ref "R5") (pin "2") (pinfunction "2_2") (pintype "passive"))
    )
    (net (code "43") (name "Net-(IC5-VIN+)") (class "Default")
      (node (ref "C13") (pin "2") (pinfunction "2_2") (pintype "passive"))
      (node (ref "IC5") (pin "8") (pinfunction "VIN+_8") (pintype "bidirectional"))
      (node (ref "R15") (pin "1") (pinfunction "1_1") (pintype "passive"))
    )
    (net (code "44") (name "Net-(IC5-VIN-)") (class "Default")
      (node (ref "C13") (pin "1") (pinfunction "1_1") (pintype "passive"))
      (node (ref "IC5") (pin "7") (pinfunction "VIN-_7") (pintype "bidirectional"))
      (node (ref "R14") (pin "1") (pinfunction "1_1") (pintype "passive"))
    )
    (net (code "45") (name "Net-(IC6--IP)") (class "Default")
      (node (ref "IC6") (pin "4") (pinfunction "-IP_4") (pintype "bidirectional"))
      (node (ref "R26") (pin "1") (pinfunction "1_1") (pintype "passive"))
      (node (ref "R27") (pin "2") (pinfunction "2_2") (pintype "passive"))
    )
    (net (code "46") (name "Net-(IC6-OP)") (class "Default")
      (node (ref "IC6") (pin "1") (pinfunction "OP_1") (pintype "bidirectional"))
      (node (ref "Q9") (pin "P$4-G") (pinfunction "G_P$4-G") (pintype "passive"))
    )
    (net (code "47") (name "Net-(IC7--IP)") (class "Default")
      (node (ref "IC7") (pin "4") (pinfunction "-IP_4") (pintype "bidirectional"))
      (node (ref "R10") (pin "2") (pinfunction "2_2") (pintype "passive"))
      (node (ref "R3") (pin "1") (pinfunction "1_1") (pintype "passive"))
    )
    (net (code "48") (name "Net-(IC7-OP)") (class "Default")
      (node (ref "IC7") (pin "1") (pinfunction "OP_1") (pintype "bidirectional"))
      (node (ref "Q3") (pin "P$4-G") (pinfunction "G_P$4-G") (pintype "passive"))
    )
    (net (code "49") (name "Net-(IC9-ALERT|BUSY)") (class "Default")
      (node (ref "IC9") (pin "P$17") (pinfunction "ALERT|BUSY_P$17") (pintype "bidirectional"))
      (node (ref "R12") (pin "2") (pinfunction "2_2") (pintype "passive"))
    )
    (net (code "50") (name "Net-(IC9-VIN_6)") (class "Default")
      (node (ref "IC9") (pin "P$12") (pinfunction "VIN_6_P$12") (pintype "bidirectional"))
      (node (ref "R33") (pin "1") (pinfunction "1_1") (pintype "passive"))
      (node (ref "R34") (pin "2") (pinfunction "2_2") (pintype "passive"))
    )
    (net (code "51") (name "Net-(IC9-VIN_8)") (class "Default")
      (node (ref "IC9") (pin "P$11") (pinfunction "VIN_8_P$11") (pintype "bidirectional"))
      (node (ref "R35") (pin "1") (pinfunction "1_1") (pintype "passive"))
      (node (ref "R36") (pin "2") (pinfunction "2_2") (pintype "passive"))
    )
    (net (code "52") (name "Net-(IC10-CIN1)") (class "Default")
      (node (ref "IC10") (pin "P$3") (pinfunction "CIN1_P$3") (pintype "bidirectional"))
      (node (ref "R30") (pin "1") (pinfunction "1_1") (pintype "passive"))
      (node (ref "R31") (pin "2") (pinfunction "2_2") (pintype "passive"))
    )
    (net (code "53") (name "Net-(IC10-CIN2)") (class "Default")
      (node (ref "IC10") (pin "P$4") (pinfunction "CIN2_P$4") (pintype "bidirectional"))
      (node (ref "R29") (pin "1") (pinfunction "1_1") (pintype "passive"))
      (node (ref "R32") (pin "2") (pinfunction "2_2") (pintype "passive"))
    )
    (net (code "54") (name "Net-(IC10-COT2)") (class "Default")
      (node (ref "IC10") (pin "P$7") (pinfunction "COT2_P$7") (pintype "bidirectional"))
      (node (ref "Q4") (pin "P$4-G") (pinfunction "G_P$4-G") (pintype "passive"))
      (node (ref "R39") (pin "1") (pinfunction "1_1") (pintype "passive"))
    )
    (net (code "55") (name "Net-(IC10-OUT)") (class "Default")
      (node (ref "IC10") (pin "P$2") (pinfunction "OUT_P$2") (pintype "bidirectional"))
      (node (ref "R29") (pin "2") (pinfunction "2_2") (pintype "passive"))
      (node (ref "R30") (pin "2") (pinfunction "2_2") (pintype "passive"))
    )
    (net (code "56") (name "Net-(IC10-RS+)") (class "Default")
      (node (ref "C4") (pin "+") (pinfunction "+_+") (pintype "passive"))
      (node (ref "D1") (pin "P$1-CATHODE") (pinfunction "P$1-CATHODE_P$1-CATHODE") (pintype "bidirectional"))
      (node (ref "IC10") (pin "P$10") (pinfunction "RS+_P$10") (pintype "bidirectional"))
      (node (ref "R1") (pin "2") (pinfunction "2_2") (pintype "passive"))
      (node (ref "R37") (pin "2") (pinfunction "2_2") (pintype "passive"))
    )
    (net (code "57") (name "Net-(IC10-VCC)") (class "Default")
      (node (ref "C17") (pin "1") (pinfunction "1_1") (pintype "passive"))
      (node (ref "IC10") (pin "P$1") (pinfunction "VCC_P$1") (pintype "bidirectional"))
      (node (ref "IC11") (pin "5") (pinfunction "VOUT_5") (pintype "bidirectional"))
    )
    (net (code "58") (name "Net-(IC11-ENA)") (class "Default")
      (node (ref "C18") (pin "1") (pinfunction "1_1") (pintype "passive"))
      (node (ref "H1") (pin "4") (pinfunction "4_4") (pintype "bidirectional"))
      (node (ref "IC11") (pin "1") (pinfunction "VIN_1") (pintype "bidirectional"))
      (node (ref "IC11") (pin "3") (pinfunction "ENA_3") (pintype "bidirectional"))
      (node (ref "Q4") (pin "P$1-S") (pinfunction "S_P$1-S") (pintype "passive"))
      (node (ref "Q4") (pin "P$2-S") (pinfunction "S_P$2-S") (pintype "passive"))
      (node (ref "Q4") (pin "P$3-S") (pinfunction "S_P$3-S") (pintype "passive"))
      (node (ref "Q6") (pin "P$1-S") (pinfunction "S_P$1-S") (pintype "passive"))
      (node (ref "Q6") (pin "P$2-S") (pinfunction "S_P$2-S") (pintype "passive"))
      (node (ref "Q6") (pin "P$3-S") (pinfunction "S_P$3-S") (pintype "passive"))
      (node (ref "Q8") (pin "P$1-S") (pinfunction "S_P$1-S") (pintype "passive"))
      (node (ref "Q8") (pin "P$2-S") (pinfunction "S_P$2-S") (pintype "passive"))
      (node (ref "Q8") (pin "P$3-S") (pinfunction "S_P$3-S") (pintype "passive"))
      (node (ref "R13") (pin "2") (pinfunction "2_2") (pintype "passive"))
      (node (ref "R14") (pin "2") (pinfunction "2_2") (pintype "passive"))
      (node (ref "R24") (pin "2") (pinfunction "2_2") (pintype "passive"))
      (node (ref "R39") (pin "2") (pinfunction "2_2") (pintype "passive"))
      (node (ref "R6") (pin "2") (pinfunction "2_2") (pintype "passive"))
    )
    (net (code "59") (name "Net-(IC12-VOUT)") (class "Default")
      (node (ref "C19") (pin "1") (pinfunction "1_1") (pintype "passive"))
      (node (ref "C20") (pin "1") (pinfunction "1_1") (pintype "passive"))
      (node (ref "IC12") (pin "5") (pinfunction "VOUT_5") (pintype "bidirectional"))
      (node (ref "IC9") (pin "P$2") (pinfunction "VDD_P$2") (pintype "bidirectional"))
      (node (ref "IC9") (pin "P$5") (pinfunction "VDD_P$5") (pintype "bidirectional"))
      (node (ref "IC9") (pin "P$6") (pinfunction "VREF_IN_P$6") (pintype "bidirectional"))
    )
    (net (code "60") (name "unconnected-(H1-Pad5)") (class "Default")
      (node (ref "H1") (pin "5") (pinfunction "5_5") (pintype "bidirectional"))
    )
    (net (code "61") (name "unconnected-(H1-Pad7)") (class "Default")
      (node (ref "H1") (pin "7") (pinfunction "7_7") (pintype "bidirectional"))
    )
    (net (code "62") (name "unconnected-(H1-Pad9)") (class "Default")
      (node (ref "H1") (pin "9") (pinfunction "9_9") (pintype "bidirectional"))
    )
    (net (code "63") (name "unconnected-(H1-Pad11)") (class "Default")
      (node (ref "H1") (pin "11") (pinfunction "11_11") (pintype "bidirectional"))
    )
    (net (code "64") (name "unconnected-(H1-Pad13)") (class "Default")
      (node (ref "H1") (pin "13") (pinfunction "13_13") (pintype "bidirectional"))
    )
    (net (code "65") (name "unconnected-(H1-Pad14)") (class "Default")
      (node (ref "H1") (pin "14") (pinfunction "14_14") (pintype "bidirectional"))
    )
    (net (code "66") (name "unconnected-(H1-Pad15)") (class "Default")
      (node (ref "H1") (pin "15") (pinfunction "15_15") (pintype "bidirectional"))
    )
    (net (code "67") (name "unconnected-(H1-Pad17)") (class "Default")
      (node (ref "H1") (pin "17") (pinfunction "17_17") (pintype "bidirectional"))
    )
    (net (code "68") (name "unconnected-(H1-Pad18)") (class "Default")
      (node (ref "H1") (pin "18") (pinfunction "18_18") (pintype "bidirectional"))
    )
    (net (code "69") (name "unconnected-(H1-Pad19)") (class "Default")
      (node (ref "H1") (pin "19") (pinfunction "19_19") (pintype "bidirectional"))
    )
    (net (code "70") (name "unconnected-(H1-Pad21)") (class "Default")
      (node (ref "H1") (pin "21") (pinfunction "21_21") (pintype "bidirectional"))
    )
    (net (code "71") (name "unconnected-(H1-Pad23)") (class "Default")
      (node (ref "H1") (pin "23") (pinfunction "23_23") (pintype "bidirectional"))
    )
    (net (code "72") (name "unconnected-(H1-Pad25)") (class "Default")
      (node (ref "H1") (pin "25") (pinfunction "25_25") (pintype "bidirectional"))
    )
    (net (code "73") (name "unconnected-(H1-Pad27)") (class "Default")
      (node (ref "H1") (pin "27") (pinfunction "27_27") (pintype "bidirectional"))
    )
    (net (code "74") (name "unconnected-(H1-Pad32)") (class "Default")
      (node (ref "H1") (pin "32") (pinfunction "32_32") (pintype "bidirectional"))
    )
    (net (code "75") (name "unconnected-(H1-Pad34)") (class "Default")
      (node (ref "H1") (pin "34") (pinfunction "34_34") (pintype "bidirectional"))
    )
    (net (code "76") (name "unconnected-(H1-Pad39)") (class "Default")
      (node (ref "H1") (pin "39") (pinfunction "39_39") (pintype "bidirectional"))
    )
    (net (code "77") (name "unconnected-(H1-Pad42)") (class "Default")
      (node (ref "H1") (pin "42") (pinfunction "42_42") (pintype "bidirectional"))
    )
    (net (code "78") (name "unconnected-(H1-Pad43)") (class "Default")
      (node (ref "H1") (pin "43") (pinfunction "43_43") (pintype "bidirectional"))
    )
    (net (code "79") (name "unconnected-(H1-Pad44)") (class "Default")
      (node (ref "H1") (pin "44") (pinfunction "44_44") (pintype "bidirectional"))
    )
    (net (code "80") (name "unconnected-(H1-Pad46)") (class "Default")
      (node (ref "H1") (pin "46") (pinfunction "46_46") (pintype "bidirectional"))
    )
    (net (code "81") (name "unconnected-(H1-Pad47)") (class "Default")
      (node (ref "H1") (pin "47") (pinfunction "47_47") (pintype "bidirectional"))
    )
    (net (code "82") (name "unconnected-(H1-Pad48)") (class "Default")
      (node (ref "H1") (pin "48") (pinfunction "48_48") (pintype "bidirectional"))
    )
    (net (code "83") (name "unconnected-(H1-Pad51)") (class "Default")
      (node (ref "H1") (pin "51") (pinfunction "51_51") (pintype "bidirectional"))
    )
    (net (code "84") (name "unconnected-(H1-Pad52)") (class "Default")
      (node (ref "H1") (pin "52") (pinfunction "52_52") (pintype "bidirectional"))
    )
    (net (code "85") (name "unconnected-(H2-Pad1)") (class "Default")
      (node (ref "H2") (pin "1") (pinfunction "1_1") (pintype "bidirectional"))
    )
    (net (code "86") (name "unconnected-(H2-Pad3)") (class "Default")
      (node (ref "H2") (pin "3") (pinfunction "3_3") (pintype "bidirectional"))
    )
    (net (code "87") (name "unconnected-(H2-Pad4)") (class "Default")
      (node (ref "H2") (pin "4") (pinfunction "4_4") (pintype "bidirectional"))
    )
    (net (code "88") (name "unconnected-(H2-Pad5)") (class "Default")
      (node (ref "H2") (pin "5") (pinfunction "5_5") (pintype "bidirectional"))
    )
    (net (code "89") (name "unconnected-(H2-Pad6)") (class "Default")
      (node (ref "H2") (pin "6") (pinfunction "6_6") (pintype "bidirectional"))
    )
    (net (code "90") (name "unconnected-(H2-Pad7)") (class "Default")
      (node (ref "H2") (pin "7") (pinfunction "7_7") (pintype "bidirectional"))
    )
    (net (code "91") (name "unconnected-(H2-Pad8)") (class "Default")
      (node (ref "H2") (pin "8") (pinfunction "8_8") (pintype "bidirectional"))
    )
    (net (code "92") (name "unconnected-(H2-Pad9)") (class "Default")
      (node (ref "H2") (pin "9") (pinfunction "9_9") (pintype "bidirectional"))
    )
    (net (code "93") (name "unconnected-(H2-Pad10)") (class "Default")
      (node (ref "H2") (pin "10") (pinfunction "10_10") (pintype "bidirectional"))
    )
    (net (code "94") (name "unconnected-(H2-Pad11)") (class "Default")
      (node (ref "H2") (pin "11") (pinfunction "11_11") (pintype "bidirectional"))
    )
    (net (code "95") (name "unconnected-(H2-Pad12)") (class "Default")
      (node (ref "H2") (pin "12") (pinfunction "12_12") (pintype "bidirectional"))
    )
    (net (code "96") (name "unconnected-(H2-Pad13)") (class "Default")
      (node (ref "H2") (pin "13") (pinfunction "13_13") (pintype "bidirectional"))
    )
    (net (code "97") (name "unconnected-(H2-Pad14)") (class "Default")
      (node (ref "H2") (pin "14") (pinfunction "14_14") (pintype "bidirectional"))
    )
    (net (code "98") (name "unconnected-(H2-Pad15)") (class "Default")
      (node (ref "H2") (pin "15") (pinfunction "15_15") (pintype "bidirectional"))
    )
    (net (code "99") (name "unconnected-(H2-Pad16)") (class "Default")
      (node (ref "H2") (pin "16") (pinfunction "16_16") (pintype "bidirectional"))
    )
    (net (code "100") (name "unconnected-(H2-Pad21)") (class "Default")
      (node (ref "H2") (pin "21") (pinfunction "21_21") (pintype "bidirectional"))
    )
    (net (code "101") (name "unconnected-(H2-Pad22)") (class "Default")
      (node (ref "H2") (pin "22") (pinfunction "22_22") (pintype "bidirectional"))
    )
    (net (code "102") (name "unconnected-(H2-Pad23)") (class "Default")
      (node (ref "H2") (pin "23") (pinfunction "23_23") (pintype "bidirectional"))
    )
    (net (code "103") (name "unconnected-(H2-Pad24)") (class "Default")
      (node (ref "H2") (pin "24") (pinfunction "24_24") (pintype "bidirectional"))
    )
    (net (code "104") (name "unconnected-(H2-Pad25)") (class "Default")
      (node (ref "H2") (pin "25") (pinfunction "25_25") (pintype "bidirectional"))
    )
    (net (code "105") (name "unconnected-(H2-Pad26)") (class "Default")
      (node (ref "H2") (pin "26") (pinfunction "26_26") (pintype "bidirectional"))
    )
    (net (code "106") (name "unconnected-(H2-Pad27)") (class "Default")
      (node (ref "H2") (pin "27") (pinfunction "27_27") (pintype "bidirectional"))
    )
    (net (code "107") (name "unconnected-(H2-Pad28)") (class "Default")
      (node (ref "H2") (pin "28") (pinfunction "28_28") (pintype "bidirectional"))
    )
    (net (code "108") (name "unconnected-(H2-Pad29)") (class "Default")
      (node (ref "H2") (pin "29") (pinfunction "29_29") (pintype "bidirectional"))
    )
    (net (code "109") (name "unconnected-(H2-Pad30)") (class "Default")
      (node (ref "H2") (pin "30") (pinfunction "30_30") (pintype "bidirectional"))
    )
    (net (code "110") (name "unconnected-(H2-Pad32)") (class "Default")
      (node (ref "H2") (pin "32") (pinfunction "32_32") (pintype "bidirectional"))
    )
    (net (code "111") (name "unconnected-(H2-Pad34)") (class "Default")
      (node (ref "H2") (pin "34") (pinfunction "34_34") (pintype "bidirectional"))
    )
    (net (code "112") (name "unconnected-(H2-Pad35)") (class "Default")
      (node (ref "H2") (pin "35") (pinfunction "35_35") (pintype "bidirectional"))
    )
    (net (code "113") (name "unconnected-(H2-Pad37)") (class "Default")
      (node (ref "H2") (pin "37") (pinfunction "37_37") (pintype "bidirectional"))
    )
    (net (code "114") (name "unconnected-(H2-Pad38)") (class "Default")
      (node (ref "H2") (pin "38") (pinfunction "38_38") (pintype "bidirectional"))
    )
    (net (code "115") (name "unconnected-(H2-Pad39)") (class "Default")
      (node (ref "H2") (pin "39") (pinfunction "39_39") (pintype "bidirectional"))
    )
    (net (code "116") (name "unconnected-(H2-Pad40)") (class "Default")
      (node (ref "H2") (pin "40") (pinfunction "40_40") (pintype "bidirectional"))
    )
    (net (code "117") (name "unconnected-(H2-Pad41)") (class "Default")
      (node (ref "H2") (pin "41") (pinfunction "41_41") (pintype "bidirectional"))
    )
    (net (code "118") (name "unconnected-(H2-Pad42)") (class "Default")
      (node (ref "H2") (pin "42") (pinfunction "42_42") (pintype "bidirectional"))
    )
    (net (code "119") (name "unconnected-(H2-Pad43)") (class "Default")
      (node (ref "H2") (pin "43") (pinfunction "43_43") (pintype "bidirectional"))
    )
    (net (code "120") (name "unconnected-(H2-Pad44)") (class "Default")
      (node (ref "H2") (pin "44") (pinfunction "44_44") (pintype "bidirectional"))
    )
    (net (code "121") (name "unconnected-(H2-Pad45)") (class "Default")
      (node (ref "H2") (pin "45") (pinfunction "45_45") (pintype "bidirectional"))
    )
    (net (code "122") (name "unconnected-(H2-Pad46)") (class "Default")
      (node (ref "H2") (pin "46") (pinfunction "46_46") (pintype "bidirectional"))
    )
    (net (code "123") (name "unconnected-(H2-Pad47)") (class "Default")
      (node (ref "H2") (pin "47") (pinfunction "47_47") (pintype "bidirectional"))
    )
    (net (code "124") (name "unconnected-(H2-Pad48)") (class "Default")
      (node (ref "H2") (pin "48") (pinfunction "48_48") (pintype "bidirectional"))
    )
    (net (code "125") (name "unconnected-(H2-Pad49)") (class "Default")
      (node (ref "H2") (pin "49") (pinfunction "49_49") (pintype "bidirectional"))
    )
    (net (code "126") (name "unconnected-(H2-Pad50)") (class "Default")
      (node (ref "H2") (pin "50") (pinfunction "50_50") (pintype "bidirectional"))
    )
    (net (code "127") (name "unconnected-(IC8-N{slash}C-Pad4)") (class "Default")
      (node (ref "IC8") (pin "4") (pinfunction "N/C_4") (pintype "bidirectional"))
    )
    (net (code "128") (name "unconnected-(IC11-N{slash}C-Pad4)") (class "Default")
      (node (ref "IC11") (pin "4") (pinfunction "N/C_4") (pintype "bidirectional"))
    )
    (net (code "129") (name "unconnected-(IC12-N{slash}C-Pad4)") (class "Default")
      (node (ref "IC12") (pin "4") (pinfunction "N/C_4") (pintype "bidirectional"))
    )
    (net (code "130") (name "unconnected-(U$1-PadP$1)") (class "Default")
      (node (ref "U$1") (pin "P$1") (pinfunction "P$1_P$1") (pintype "bidirectional"))
    )
  )
)
